# BW1092_Power_Supply.net
KiCad netlist of a schematic drawn in Altium Designer
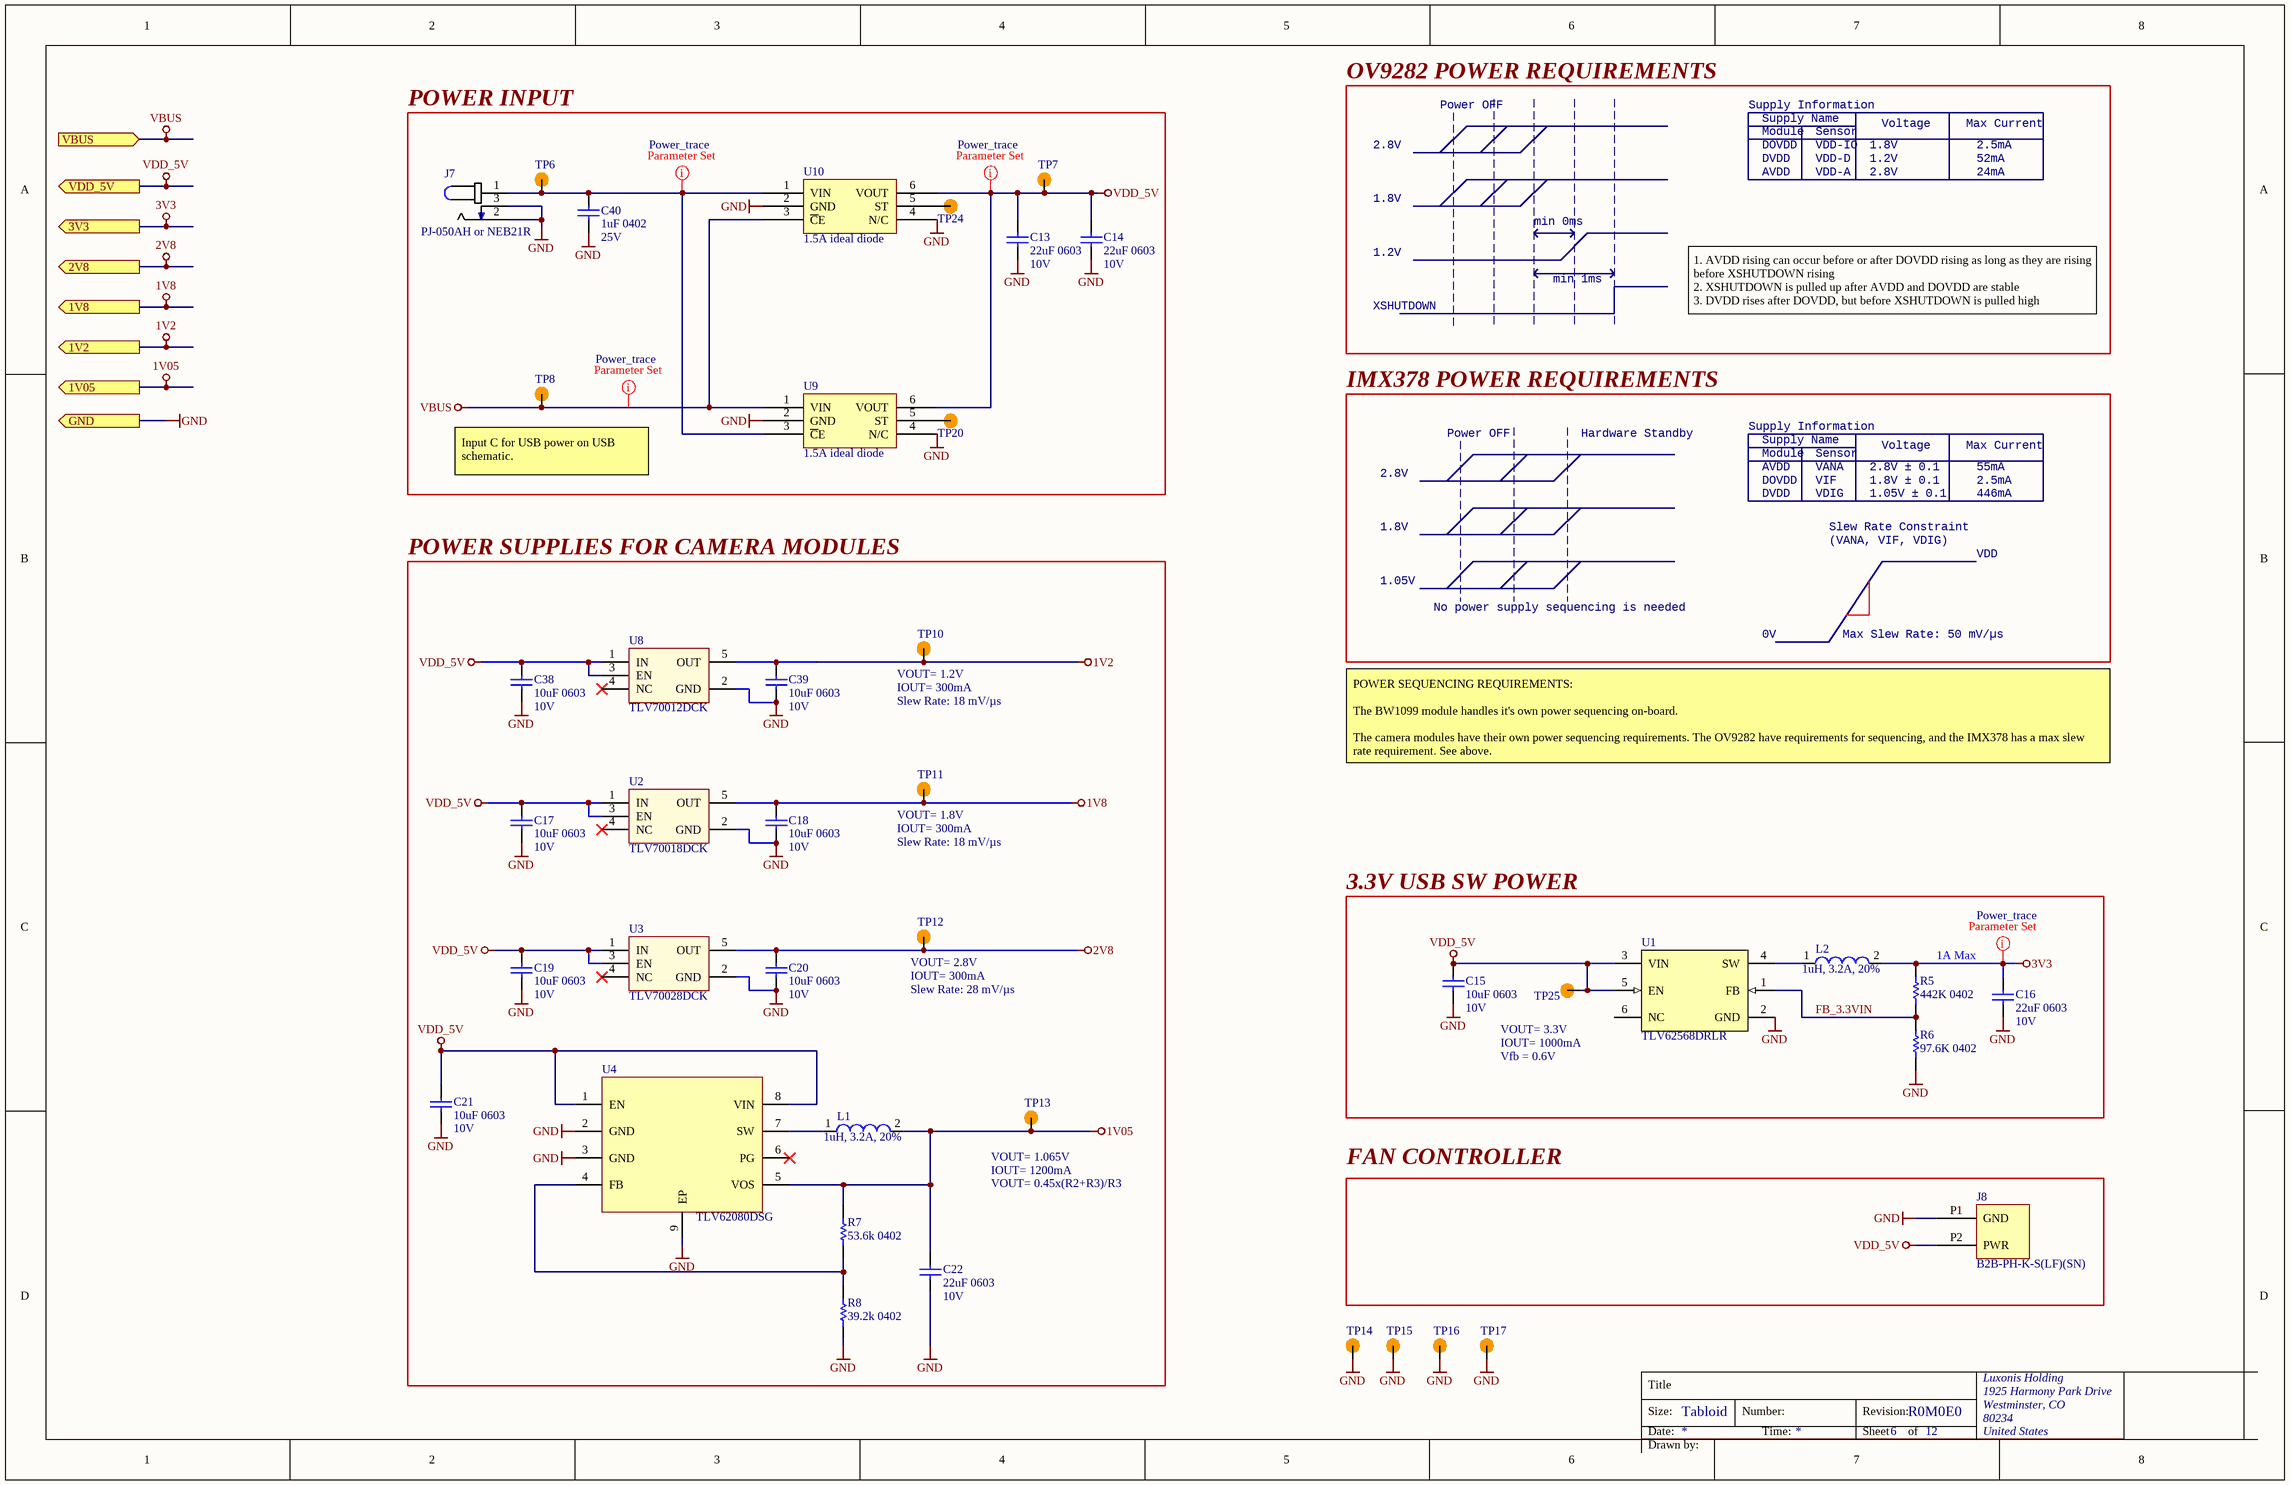
[diagram p0: BW1092_Power_Supply.SchDoc]

(export (version "E")
  (design (tool "Eeschema 10.0.6"))
  (components
    (comp (ref "C13")
      (value "22uF 0603")
      (footprint "CAP_Altium_Vault_Generic:CAPC0603(1608)100_L")
      (description "CAP CER 22UF 10V X5R 0603 20%")
      (fields (field (name "TOLERANCE") "20%") (field (name "VOLTAGE RATING") "10V"))
      (libsource (lib "LuxonisMaster") (part "GRM188R61A226ME15D"))
    )
    (comp (ref "C14")
      (value "22uF 0603")
      (footprint "CAP_Altium_Vault_Generic:CAPC0603(1608)100_L")
      (description "CAP CER 22UF 10V X5R 0603 20%")
      (fields (field (name "TOLERANCE") "20%") (field (name "VOLTAGE RATING") "10V"))
      (libsource (lib "LuxonisMaster") (part "GRM188R61A226ME15D"))
    )
    (comp (ref "C15")
      (value "10uF 0603")
      (footprint "CAP_Altium_Vault_Generic:CAPC0603(1608)100_L")
      (description "CAP CER 10UF 10V X5R 0603 20%")
      (fields (field (name "TOLERANCE") "20%") (field (name "VOLTAGE RATING") "10V"))
      (libsource (lib "LuxonisMaster") (part "GRM188R61A106ME69D"))
    )
    (comp (ref "C16")
      (value "22uF 0603")
      (footprint "CAP_Altium_Vault_Generic:CAPC0603(1608)100_N")
      (description "CAP CER 22UF 10V X5R 0603 20%")
      (fields (field (name "TOLERANCE") "20%") (field (name "VOLTAGE RATING") "10V"))
      (libsource (lib "LuxonisMaster") (part "GRM188R61A226ME15D"))
    )
    (comp (ref "C17")
      (value "10uF 0603")
      (footprint "CAP_Altium_Vault_Generic:CAPC0603(1608)100_L")
      (description "CAP CER 10UF 10V X5R 0603 20%")
      (fields (field (name "TOLERANCE") "20%") (field (name "VOLTAGE RATING") "10V"))
      (libsource (lib "LuxonisMaster") (part "GRM188R61A106ME69D"))
    )
    (comp (ref "C18")
      (value "10uF 0603")
      (footprint "CAP_Altium_Vault_Generic:CAPC0603(1608)100_L")
      (description "CAP CER 10UF 10V X5R 0603 20%")
      (fields (field (name "TOLERANCE") "20%") (field (name "VOLTAGE RATING") "10V"))
      (libsource (lib "LuxonisMaster") (part "GRM188R61A106ME69D"))
    )
    (comp (ref "C19")
      (value "10uF 0603")
      (footprint "CAP_Altium_Vault_Generic:CAPC0603(1608)100_L")
      (description "CAP CER 10UF 10V X5R 0603 20%")
      (fields (field (name "TOLERANCE") "20%") (field (name "VOLTAGE RATING") "10V"))
      (libsource (lib "LuxonisMaster") (part "GRM188R61A106ME69D"))
    )
    (comp (ref "C20")
      (value "10uF 0603")
      (footprint "CAP_Altium_Vault_Generic:CAPC0603(1608)100_L")
      (description "CAP CER 10UF 10V X5R 0603 20%")
      (fields (field (name "TOLERANCE") "20%") (field (name "VOLTAGE RATING") "10V"))
      (libsource (lib "LuxonisMaster") (part "GRM188R61A106ME69D"))
    )
    (comp (ref "C21")
      (value "10uF 0603")
      (footprint "CAP_Altium_Vault_Generic:CAPC0603(1608)100_L")
      (description "CAP CER 10UF 10V X5R 0603 20%")
      (fields (field (name "TOLERANCE") "20%") (field (name "VOLTAGE RATING") "10V"))
      (libsource (lib "LuxonisMaster") (part "GRM188R61A106ME69D"))
    )
    (comp (ref "C22")
      (value "22uF 0603")
      (footprint "CAP_Altium_Vault_Generic:CAPC0603(1608)100_L")
      (description "CAP CER 22UF 10V X5R 0603 20%")
      (fields (field (name "TOLERANCE") "20%") (field (name "VOLTAGE RATING") "10V"))
      (libsource (lib "LuxonisMaster") (part "GRM188R61A226ME15D"))
    )
    (comp (ref "C38")
      (value "10uF 0603")
      (footprint "CAP_Altium_Vault_Generic:CAPC0603(1608)100_L")
      (description "CAP CER 10UF 10V X5R 0603 20%")
      (fields (field (name "TOLERANCE") "20%") (field (name "VOLTAGE RATING") "10V"))
      (libsource (lib "LuxonisMaster") (part "GRM188R61A106ME69D"))
    )
    (comp (ref "C39")
      (value "10uF 0603")
      (footprint "CAP_Altium_Vault_Generic:CAPC0603(1608)100_L")
      (description "CAP CER 10UF 10V X5R 0603 20%")
      (fields (field (name "TOLERANCE") "20%") (field (name "VOLTAGE RATING") "10V"))
      (libsource (lib "LuxonisMaster") (part "GRM188R61A106ME69D"))
    )
    (comp (ref "C40")
      (value "1uF 0402")
      (footprint "CAP_Altium_Vault_Generic:CAPC0402(1005)70_L")
      (description "CAP CER 1UF 25V X5R 0402 10%")
      (fields
        (field (name "TOLERANCE") "10%")
        (field (name "VOLTAGE") "25V")
        (field (name "VOLTAGE RATING") "25V")
      )
      (libsource (lib "LuxonisMaster") (part "GRM155R61E105KA12D"))
    )
    (comp (ref "J7")
      (value "PJ-050AH or NEB21R")
      (footprint "LuxonisMaster:PJ-050AH/NEB21R_COMBO")
      (description "CONN POWER PIN 2 POS RA PTH Barrel jack 2.1mm x 5.5mm combo footprint")
      (libsource (lib "LuxonisMaster") (part "PJ-050AH/NEB21R_COMBO"))
    )
    (comp (ref "J8")
      (value "B2B-PH-K-S(LF)(SN)")
      (footprint "LuxonisMaster:B2B-PH-K-S(LF)(SN)")
      (description "CONN HEADER VERT 2POS 2MM")
      (fields (field (name "MANUFACTURER") "JST"))
      (libsource (lib "LuxonisMaster") (part "B2B-PH-K-S(LF)(SN)"))
    )
    (comp (ref "L1")
      (value "1uH, 3.2A, 20%")
      (footprint "LuxonisMaster:DFE252012P-1R0M=P2")
      (description "FIXED IND 1UH 3.2A 42 MOHM SMD")
      (fields
        (field (name "MANUFACTURER") "Murata")
        (field (name "MANUFACTURER PART NUMBER") "DFE252012P-1R0M=P2")
      )
      (libsource (lib "LuxonisMaster") (part "DFE252012P-1R0M=P2"))
    )
    (comp (ref "L2")
      (value "1uH, 3.2A, 20%")
      (footprint "LuxonisMaster:DFE252012P-1R0M=P2")
      (description "FIXED IND 1UH 3.2A 42 MOHM SMD")
      (fields
        (field (name "MANUFACTURER") "Murata")
        (field (name "MANUFACTURER PART NUMBER") "DFE252012P-1R0M=P2")
      )
      (libsource (lib "LuxonisMaster") (part "DFE252012P-1R0M=P2"))
    )
    (comp (ref "R5")
      (value "442K 0402")
      (footprint "RES_Altium_Vault_Generic:RESC0402(1005)_N")
      (description "RES SMD 442K OHM 1% 1/16W 0402")
      (fields (field (name "TOLERANCE") "1%"))
      (libsource (lib "BW1092_R0M0E0") (part "CRCW0402442KFKED"))
    )
    (comp (ref "R6")
      (value "97.6K 0402")
      (footprint "RES_Altium_Vault_Generic:RESC0402(1005)_N")
      (description "RES SMD 97.6K OHM 1% 1/16W 0402")
      (fields (field (name "TOLERANCE") "1%"))
      (libsource (lib "BW1092_R0M0E0") (part "CRCW040297K6FKED"))
    )
    (comp (ref "R7")
      (value "53.6k 0402")
      (footprint "RES_Altium_Vault_Generic:RESC0402(1005)_L")
      (description "RES SMD 53.6K OHM 1% 1/16W 0402")
      (fields (field (name "TOLERANCE") "1%"))
      (libsource (lib "LuxonisMaster") (part "CRCW040253K6FKED"))
    )
    (comp (ref "R8")
      (value "39.2k 0402")
      (footprint "RES_Altium_Vault_Generic:RESC0402(1005)_L")
      (description "RES SMD 39.2K OHM 1% 1/16W 0402")
      (fields (field (name "TOLERANCE") "1%"))
      (libsource (lib "LuxonisMaster") (part "CRCW040239K2FKED"))
    )
    (comp (ref "TP6")
      (value "TP100_200_NS")
      (footprint "LuxonisMaster:TP100_200_NS")
      (libsource (lib "LuxonisMaster") (part "TEST_POINT"))
    )
    (comp (ref "TP7")
      (value "TP100_200_NS")
      (footprint "LuxonisMaster:TP100_200_NS")
      (libsource (lib "LuxonisMaster") (part "TEST_POINT"))
    )
    (comp (ref "TP8")
      (value "TP100_200_NS")
      (footprint "LuxonisMaster:TP100_200_NS")
      (libsource (lib "LuxonisMaster") (part "TEST_POINT"))
    )
    (comp (ref "TP10")
      (value "TP100_200_NS")
      (footprint "LuxonisMaster:TP100_200_NS")
      (libsource (lib "LuxonisMaster") (part "TEST_POINT"))
    )
    (comp (ref "TP11")
      (value "TP100_200_NS")
      (footprint "LuxonisMaster:TP100_200_NS")
      (libsource (lib "LuxonisMaster") (part "TEST_POINT"))
    )
    (comp (ref "TP12")
      (value "TP100_200_NS")
      (footprint "LuxonisMaster:TP100_200_NS")
      (libsource (lib "LuxonisMaster") (part "TEST_POINT"))
    )
    (comp (ref "TP13")
      (value "TP100_200_NS")
      (footprint "LuxonisMaster:TP100_200_NS")
      (libsource (lib "LuxonisMaster") (part "TEST_POINT"))
    )
    (comp (ref "TP14")
      (value "TP100_200_NS")
      (footprint "LuxonisMaster:TP100_200_NS")
      (libsource (lib "LuxonisMaster") (part "TEST_POINT"))
    )
    (comp (ref "TP15")
      (value "TP100_200_NS")
      (footprint "LuxonisMaster:TP100_200_NS")
      (libsource (lib "LuxonisMaster") (part "TEST_POINT"))
    )
    (comp (ref "TP16")
      (value "TP100_200_NS")
      (footprint "LuxonisMaster:TP100_200_NS")
      (libsource (lib "LuxonisMaster") (part "TEST_POINT"))
    )
    (comp (ref "TP17")
      (value "TP100_200_NS")
      (footprint "LuxonisMaster:TP100_200_NS")
      (libsource (lib "LuxonisMaster") (part "TEST_POINT"))
    )
    (comp (ref "TP20")
      (value "TP100_200_NS")
      (footprint "LuxonisMaster:TP100_200_NS")
      (libsource (lib "LuxonisMaster") (part "TEST_POINT"))
    )
    (comp (ref "TP24")
      (value "TP100_200_NS")
      (footprint "LuxonisMaster:TP100_200_NS")
      (libsource (lib "LuxonisMaster") (part "TEST_POINT"))
    )
    (comp (ref "TP25")
      (value "TP100_200_NS")
      (footprint "LuxonisMaster:TP100_200_NS")
      (libsource (lib "LuxonisMaster") (part "TEST_POINT"))
    )
    (comp (ref "U1")
      (value "TLV62568DRLR")
      (footprint "BW1092_R0M0E0:TLV62568DRLR")
      (description "IC REG BUCK ADJ 1A SOT563-6")
      (libsource (lib "BW1092_R0M0E0") (part "TLV62568DRLR"))
    )
    (comp (ref "U2")
      (value "TLV70018DCK")
      (footprint "LuxonisMaster:TLV70018DCK")
      (description "IC REG LINEAR 1.8V 200MA SC70-5 Linear Voltage Regulator IC  1 Output  200mA SC-70-5")
      (libsource (lib "LuxonisMaster") (part "TLV70018DCK"))
    )
    (comp (ref "U3")
      (value "TLV70028DCK")
      (footprint "LuxonisMaster:TLV70028DCK")
      (description "IC REG LINEAR 2.8V 200MA SC70-5 Linear Voltage Regulator IC  1 Output  200mA SC-70-5")
      (libsource (lib "LuxonisMaster") (part "TLV70028DCK"))
    )
    (comp (ref "U4")
      (value "TLV62080DSG")
      (footprint "LuxonisMaster:TLV62080DSG")
      (description "IC REG BUCK ADJ 1.2A SYNC 8WSON")
      (libsource (lib "LuxonisMaster") (part "TLV62080DSG"))
    )
    (comp (ref "U8")
      (value "TLV70012DCK")
      (footprint "LuxonisMaster:TLV70012DCK")
      (description "IC REG LINEAR 1.2V 200MA SC70-5")
      (libsource (lib "LuxonisMaster") (part "TLV70012DCK"))
    )
    (comp (ref "U9")
      (value "1.5A ideal diode")
      (footprint "BW1098OBC_R2M0E2:LM66100DCKR")
      (description "IC OR CTRLR IDEAL DIODE SC70-6")
      (libsource (lib "BW1098OBC_R2M0E2") (part "LM66100DCKR"))
    )
    (comp (ref "U10")
      (value "1.5A ideal diode")
      (footprint "BW1098OBC_R2M0E2:LM66100DCKR")
      (description "IC OR CTRLR IDEAL DIODE SC70-6")
      (libsource (lib "BW1098OBC_R2M0E2") (part "LM66100DCKR"))
    )
  )
  (nets
    (net (code "1") (name "/FB_3.3VIN") (class "Default")
      (node (ref "R5") (pin "1") (pinfunction "1_1") (pintype "passive"))
      (node (ref "R6") (pin "2") (pinfunction "2_2") (pintype "passive"))
      (node (ref "U1") (pin "1") (pinfunction "FB_1") (pintype "input"))
    )
    (net (code "2") (name "1V2") (class "Default")
      (node (ref "C39") (pin "2") (pinfunction "2_2") (pintype "passive"))
      (node (ref "TP10") (pin "1") (pintype "passive"))
      (node (ref "U8") (pin "5") (pinfunction "OUT_5") (pintype "passive"))
    )
    (net (code "3") (name "1V05") (class "Default")
      (node (ref "C22") (pin "2") (pinfunction "2_2") (pintype "passive"))
      (node (ref "L1") (pin "2") (pinfunction "2_2") (pintype "passive"))
      (node (ref "R7") (pin "2") (pinfunction "2_2") (pintype "passive"))
      (node (ref "TP13") (pin "1") (pintype "passive"))
      (node (ref "U4") (pin "5") (pinfunction "VOS_5") (pintype "passive"))
    )
    (net (code "4") (name "1V8") (class "Default")
      (node (ref "C18") (pin "2") (pinfunction "2_2") (pintype "passive"))
      (node (ref "TP11") (pin "1") (pintype "passive"))
      (node (ref "U2") (pin "5") (pinfunction "OUT_5") (pintype "passive"))
    )
    (net (code "5") (name "2V8") (class "Default")
      (node (ref "C20") (pin "2") (pinfunction "2_2") (pintype "passive"))
      (node (ref "TP12") (pin "1") (pintype "passive"))
      (node (ref "U3") (pin "5") (pinfunction "OUT_5") (pintype "passive"))
    )
    (net (code "6") (name "3V3") (class "Default")
      (node (ref "C16") (pin "1") (pinfunction "1_1") (pintype "passive"))
      (node (ref "L2") (pin "2") (pinfunction "2_2") (pintype "passive"))
      (node (ref "R5") (pin "2") (pinfunction "2_2") (pintype "passive"))
    )
    (net (code "7") (name "GND") (class "Default")
      (node (ref "C13") (pin "1") (pinfunction "1_1") (pintype "passive"))
      (node (ref "C14") (pin "1") (pinfunction "1_1") (pintype "passive"))
      (node (ref "C15") (pin "1") (pinfunction "1_1") (pintype "passive"))
      (node (ref "C16") (pin "2") (pinfunction "2_2") (pintype "passive"))
      (node (ref "C17") (pin "1") (pinfunction "1_1") (pintype "passive"))
      (node (ref "C18") (pin "1") (pinfunction "1_1") (pintype "passive"))
      (node (ref "C19") (pin "1") (pinfunction "1_1") (pintype "passive"))
      (node (ref "C20") (pin "1") (pinfunction "1_1") (pintype "passive"))
      (node (ref "C21") (pin "1") (pinfunction "1_1") (pintype "passive"))
      (node (ref "C22") (pin "1") (pinfunction "1_1") (pintype "passive"))
      (node (ref "C38") (pin "1") (pinfunction "1_1") (pintype "passive"))
      (node (ref "C39") (pin "1") (pinfunction "1_1") (pintype "passive"))
      (node (ref "C40") (pin "1") (pinfunction "1_1") (pintype "passive"))
      (node (ref "J7") (pin "2") (pinfunction "2_2") (pintype "passive"))
      (node (ref "J7") (pin "3") (pinfunction "3_3") (pintype "passive"))
      (node (ref "J8") (pin "P1") (pinfunction "GND_P1") (pintype "passive"))
      (node (ref "R6") (pin "1") (pinfunction "1_1") (pintype "passive"))
      (node (ref "R8") (pin "1") (pinfunction "1_1") (pintype "passive"))
      (node (ref "TP14") (pin "1") (pintype "passive"))
      (node (ref "TP15") (pin "1") (pintype "passive"))
      (node (ref "TP16") (pin "1") (pintype "passive"))
      (node (ref "TP17") (pin "1") (pintype "passive"))
      (node (ref "U1") (pin "2") (pinfunction "GND_2") (pintype "power_in"))
      (node (ref "U10") (pin "2") (pinfunction "GND_2") (pintype "passive"))
      (node (ref "U10") (pin "4") (pinfunction "N/C_4") (pintype "passive"))
      (node (ref "U2") (pin "2") (pinfunction "GND_2") (pintype "passive"))
      (node (ref "U3") (pin "2") (pinfunction "GND_2") (pintype "passive"))
      (node (ref "U4") (pin "2") (pinfunction "GND_2") (pintype "passive"))
      (node (ref "U4") (pin "3") (pinfunction "GND_3") (pintype "passive"))
      (node (ref "U4") (pin "9") (pinfunction "EP_9") (pintype "passive"))
      (node (ref "U8") (pin "2") (pinfunction "GND_2") (pintype "passive"))
      (node (ref "U9") (pin "2") (pinfunction "GND_2") (pintype "passive"))
      (node (ref "U9") (pin "4") (pinfunction "N/C_4") (pintype "passive"))
    )
    (net (code "8") (name "Net-(U1-SW)") (class "Default")
      (node (ref "L2") (pin "1") (pinfunction "1_1") (pintype "passive"))
      (node (ref "U1") (pin "4") (pinfunction "SW_4") (pintype "power_in"))
    )
    (net (code "9") (name "Net-(U4-FB)") (class "Default")
      (node (ref "R7") (pin "1") (pinfunction "1_1") (pintype "passive"))
      (node (ref "R8") (pin "2") (pinfunction "2_2") (pintype "passive"))
      (node (ref "U4") (pin "4") (pinfunction "FB_4") (pintype "passive"))
    )
    (net (code "10") (name "Net-(U4-SW)") (class "Default")
      (node (ref "L1") (pin "1") (pinfunction "1_1") (pintype "passive"))
      (node (ref "U4") (pin "7") (pinfunction "SW_7") (pintype "passive"))
    )
    (net (code "11") (name "Net-(U9-ST)") (class "Default")
      (node (ref "TP20") (pin "1") (pintype "passive"))
      (node (ref "U9") (pin "5") (pinfunction "ST_5") (pintype "passive"))
    )
    (net (code "12") (name "Net-(U10-ST)") (class "Default")
      (node (ref "TP24") (pin "1") (pintype "passive"))
      (node (ref "U10") (pin "5") (pinfunction "ST_5") (pintype "passive"))
    )
    (net (code "13") (name "Net-(U10-VIN)") (class "Default")
      (node (ref "C40") (pin "2") (pinfunction "2_2") (pintype "passive"))
      (node (ref "J7") (pin "1") (pinfunction "1_1") (pintype "passive"))
      (node (ref "TP6") (pin "1") (pintype "passive"))
      (node (ref "U10") (pin "1") (pinfunction "VIN_1") (pintype "passive"))
      (node (ref "U9") (pin "3") (pinfunction "~{C}E_3") (pintype "passive"))
    )
    (net (code "14") (name "VBUS") (class "Default")
      (node (ref "TP8") (pin "1") (pintype "passive"))
      (node (ref "U10") (pin "3") (pinfunction "~{C}E_3") (pintype "passive"))
      (node (ref "U9") (pin "1") (pinfunction "VIN_1") (pintype "passive"))
    )
    (net (code "15") (name "VDD_5V") (class "Default")
      (node (ref "C13") (pin "2") (pinfunction "2_2") (pintype "passive"))
      (node (ref "C14") (pin "2") (pinfunction "2_2") (pintype "passive"))
      (node (ref "C15") (pin "2") (pinfunction "2_2") (pintype "passive"))
      (node (ref "C17") (pin "2") (pinfunction "2_2") (pintype "passive"))
      (node (ref "C19") (pin "2") (pinfunction "2_2") (pintype "passive"))
      (node (ref "C21") (pin "2") (pinfunction "2_2") (pintype "passive"))
      (node (ref "C38") (pin "2") (pinfunction "2_2") (pintype "passive"))
      (node (ref "J8") (pin "P2") (pinfunction "PWR_P2") (pintype "passive"))
      (node (ref "TP25") (pin "1") (pintype "passive"))
      (node (ref "TP7") (pin "1") (pintype "passive"))
      (node (ref "U1") (pin "3") (pinfunction "VIN_3") (pintype "power_in"))
      (node (ref "U1") (pin "5") (pinfunction "EN_5") (pintype "input"))
      (node (ref "U10") (pin "6") (pinfunction "VOUT_6") (pintype "passive"))
      (node (ref "U2") (pin "1") (pinfunction "IN_1") (pintype "passive"))
      (node (ref "U2") (pin "3") (pinfunction "EN_3") (pintype "passive"))
      (node (ref "U3") (pin "1") (pinfunction "IN_1") (pintype "passive"))
      (node (ref "U3") (pin "3") (pinfunction "EN_3") (pintype "passive"))
      (node (ref "U4") (pin "1") (pinfunction "EN_1") (pintype "passive"))
      (node (ref "U4") (pin "8") (pinfunction "VIN_8") (pintype "passive"))
      (node (ref "U8") (pin "1") (pinfunction "IN_1") (pintype "passive"))
      (node (ref "U8") (pin "3") (pinfunction "EN_3") (pintype "passive"))
      (node (ref "U9") (pin "6") (pinfunction "VOUT_6") (pintype "passive"))
    )
    (net (code "16") (name "unconnected-(U1-NC-Pad6)") (class "Default")
      (node (ref "U1") (pin "6") (pinfunction "NC_6") (pintype "passive"))
    )
    (net (code "17") (name "unconnected-(U2-NC-Pad4)") (class "Default")
      (node (ref "U2") (pin "4") (pinfunction "NC_4") (pintype "passive+no_connect"))
    )
    (net (code "18") (name "unconnected-(U3-NC-Pad4)") (class "Default")
      (node (ref "U3") (pin "4") (pinfunction "NC_4") (pintype "passive+no_connect"))
    )
    (net (code "19") (name "unconnected-(U4-PG-Pad6)") (class "Default")
      (node (ref "U4") (pin "6") (pinfunction "PG_6") (pintype "passive+no_connect"))
    )
    (net (code "20") (name "unconnected-(U8-NC-Pad4)") (class "Default")
      (node (ref "U8") (pin "4") (pinfunction "NC_4") (pintype "passive+no_connect"))
    )
  )
)
